# Control.net
KiCad netlist of a schematic drawn in Altium Designer
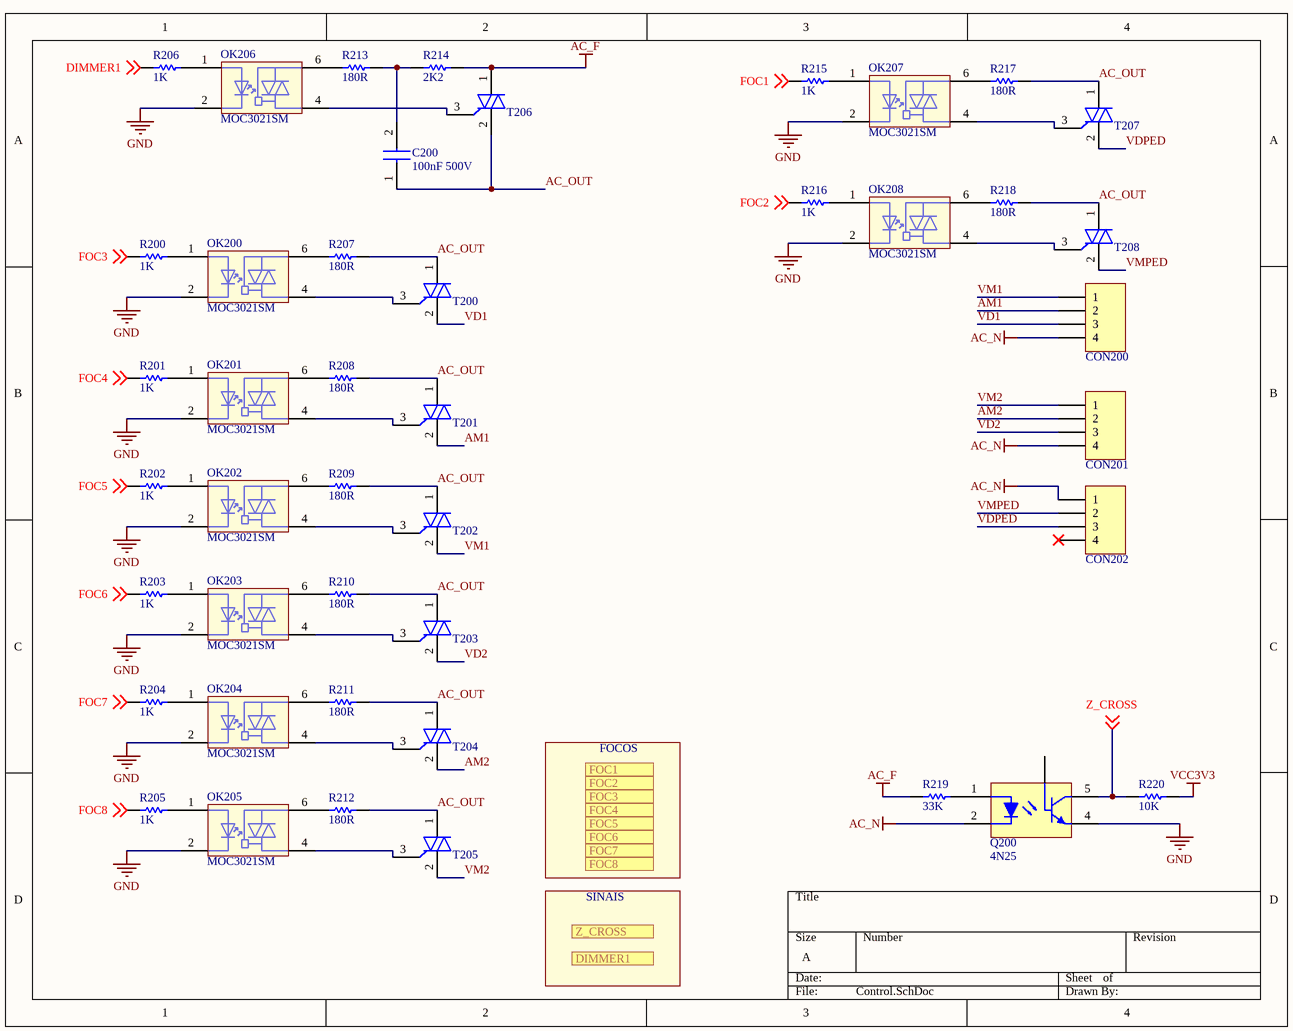
[diagram p0: Control.SchDoc]

(export (version "E")
  (design (tool "Eeschema 10.0.6"))
  (components
    (comp (ref "C200")
      (value "100nF 500V")
      (footprint "STL:CAPC3225-1210N")
      (description "CAP CER 0.1UF 500V X7R 1210")
      (fields
        (field (name "MANUFACTURER_PART_NUMBER") "C1210C106M6PACTU")
        (field (name "MOUSER PART NUMBER") "80-C1210C106M6P")
      )
      (libsource (lib "STL") (part "CAP 100nF 500V C1210C106M6PACTU 1210"))
    )
    (comp (ref "CON200")
      (value "TERM BLOCK 4POS")
      (footprint "STL:MSTBA 4G")
      (description "TERM BLOCK HDR 4POS R/A 5.08MM")
      (libsource (lib "STL") (part "TERM BLOCK HEADER 4POS R/A 5.08MM"))
    )
    (comp (ref "CON201")
      (value "TERM BLOCK 4POS")
      (footprint "STL:MSTBA 4G")
      (description "TERM BLOCK HDR 4POS R/A 5.08MM")
      (libsource (lib "STL") (part "TERM BLOCK HEADER 4POS R/A 5.08MM"))
    )
    (comp (ref "CON202")
      (value "TERM BLOCK 4POS")
      (footprint "STL:MSTBA 4G")
      (description "TERM BLOCK HDR 4POS R/A 5.08MM")
      (libsource (lib "STL") (part "TERM BLOCK HEADER 4POS R/A 5.08MM"))
    )
    (comp (ref "OK200")
      (value "MOC3021SM")
      (footprint "STL:SOP254P1016X450-6N")
      (description "OPTOCOUPLERS SMD-6 ROHS")
      (fields
        (field (name "MANUFACTURER PART NUMBER") "OR-MOC3021S")
        (field (name "MANUFACTURER") "Orient Technology")
      )
      (libsource (lib "STL") (part "OPTOISO Triac MOC3021SM SOP6N"))
    )
    (comp (ref "OK201")
      (value "MOC3021SM")
      (footprint "STL:SOP254P1016X450-6N")
      (description "OPTOCOUPLERS SMD-6 ROHS")
      (fields
        (field (name "MANUFACTURER PART NUMBER") "OR-MOC3021S")
        (field (name "MANUFACTURER") "Orient Technology")
      )
      (libsource (lib "STL") (part "OPTOISO Triac MOC3021SM SOP6N"))
    )
    (comp (ref "OK202")
      (value "MOC3021SM")
      (footprint "STL:SOP254P1016X450-6N")
      (description "OPTOCOUPLERS SMD-6 ROHS")
      (fields
        (field (name "MANUFACTURER PART NUMBER") "OR-MOC3021S")
        (field (name "MANUFACTURER") "Orient Technology")
      )
      (libsource (lib "STL") (part "OPTOISO Triac MOC3021SM SOP6N"))
    )
    (comp (ref "OK203")
      (value "MOC3021SM")
      (footprint "STL:SOP254P1016X450-6N")
      (description "OPTOCOUPLERS SMD-6 ROHS")
      (fields
        (field (name "MANUFACTURER PART NUMBER") "OR-MOC3021S")
        (field (name "MANUFACTURER") "Orient Technology")
      )
      (libsource (lib "STL") (part "OPTOISO Triac MOC3021SM SOP6N"))
    )
    (comp (ref "OK204")
      (value "MOC3021SM")
      (footprint "STL:SOP254P1016X450-6N")
      (description "OPTOCOUPLERS SMD-6 ROHS")
      (fields
        (field (name "MANUFACTURER PART NUMBER") "OR-MOC3021S")
        (field (name "MANUFACTURER") "Orient Technology")
      )
      (libsource (lib "STL") (part "OPTOISO Triac MOC3021SM SOP6N"))
    )
    (comp (ref "OK205")
      (value "MOC3021SM")
      (footprint "STL:SOP254P1016X450-6N")
      (description "OPTOCOUPLERS SMD-6 ROHS")
      (fields
        (field (name "MANUFACTURER PART NUMBER") "OR-MOC3021S")
        (field (name "MANUFACTURER") "Orient Technology")
      )
      (libsource (lib "STL") (part "OPTOISO Triac MOC3021SM SOP6N"))
    )
    (comp (ref "OK206")
      (value "MOC3021SM")
      (footprint "STL:SOP254P1016X450-6N")
      (description "OPTOCOUPLERS SMD-6 ROHS")
      (fields
        (field (name "MANUFACTURER PART NUMBER") "OR-MOC3021S")
        (field (name "MANUFACTURER") "Orient Technology")
      )
      (libsource (lib "STL") (part "OPTOISO Triac MOC3021SM SOP6N"))
    )
    (comp (ref "OK207")
      (value "MOC3021SM")
      (footprint "STL:SOP254P1016X450-6N")
      (description "OPTOCOUPLERS SMD-6 ROHS")
      (fields
        (field (name "MANUFACTURER PART NUMBER") "OR-MOC3021S")
        (field (name "MANUFACTURER") "Orient Technology")
      )
      (libsource (lib "STL") (part "OPTOISO Triac MOC3021SM SOP6N"))
    )
    (comp (ref "OK208")
      (value "MOC3021SM")
      (footprint "STL:SOP254P1016X450-6N")
      (description "OPTOCOUPLERS SMD-6 ROHS")
      (fields
        (field (name "MANUFACTURER PART NUMBER") "OR-MOC3021S")
        (field (name "MANUFACTURER") "Orient Technology")
      )
      (libsource (lib "STL") (part "OPTOISO Triac MOC3021SM SOP6N"))
    )
    (comp (ref "Q200")
      (value "4N25")
      (footprint "STL:6-SMD")
      (description "OPTOISO 4.17KV TRANS W/BASE 6SMD")
      (fields
        (field (name "MANUFACTURER") "ON Semiconductor")
        (field (name "MANUFACTURER PART NUMBER") "4N25SR2M")
      )
      (libsource (lib "STL") (part "OPTOISO 4N25S 2.5KV TRANS W/BASE 6SMD"))
    )
    (comp (ref "R200")
      (value "1K")
      (footprint "STL:CR2012-0805")
      (description "RES SMD 1K OHM 1% 1/8W 0805")
      (fields
        (field (name "MANUFACTURER") "Yageo")
        (field (name "MANUFACTURER PART NUMBER") "RC0805FR-071KL")
      )
      (libsource (lib "STL") (part "RES 1K OHM 1% 1/8W 0805 SMD"))
    )
    (comp (ref "R201")
      (value "1K")
      (footprint "STL:CR2012-0805")
      (description "RES SMD 1K OHM 1% 1/8W 0805")
      (fields
        (field (name "MANUFACTURER") "Yageo")
        (field (name "MANUFACTURER PART NUMBER") "RC0805FR-071KL")
      )
      (libsource (lib "STL") (part "RES 1K OHM 1% 1/8W 0805 SMD"))
    )
    (comp (ref "R202")
      (value "1K")
      (footprint "STL:CR2012-0805")
      (description "RES SMD 1K OHM 1% 1/8W 0805")
      (fields
        (field (name "MANUFACTURER") "Yageo")
        (field (name "MANUFACTURER PART NUMBER") "RC0805FR-071KL")
      )
      (libsource (lib "STL") (part "RES 1K OHM 1% 1/8W 0805 SMD"))
    )
    (comp (ref "R203")
      (value "1K")
      (footprint "STL:CR2012-0805")
      (description "RES SMD 1K OHM 1% 1/8W 0805")
      (fields
        (field (name "MANUFACTURER") "Yageo")
        (field (name "MANUFACTURER PART NUMBER") "RC0805FR-071KL")
      )
      (libsource (lib "STL") (part "RES 1K OHM 1% 1/8W 0805 SMD"))
    )
    (comp (ref "R204")
      (value "1K")
      (footprint "STL:CR2012-0805")
      (description "RES SMD 1K OHM 1% 1/8W 0805")
      (fields
        (field (name "MANUFACTURER") "Yageo")
        (field (name "MANUFACTURER PART NUMBER") "RC0805FR-071KL")
      )
      (libsource (lib "STL") (part "RES 1K OHM 1% 1/8W 0805 SMD"))
    )
    (comp (ref "R205")
      (value "1K")
      (footprint "STL:CR2012-0805")
      (description "RES SMD 1K OHM 1% 1/8W 0805")
      (fields
        (field (name "MANUFACTURER") "Yageo")
        (field (name "MANUFACTURER PART NUMBER") "RC0805FR-071KL")
      )
      (libsource (lib "STL") (part "RES 1K OHM 1% 1/8W 0805 SMD"))
    )
    (comp (ref "R206")
      (value "1K")
      (footprint "STL:CR2012-0805")
      (description "RES SMD 1K OHM 1% 1/8W 0805")
      (fields
        (field (name "MANUFACTURER") "Yageo")
        (field (name "MANUFACTURER PART NUMBER") "RC0805FR-071KL")
      )
      (libsource (lib "STL") (part "RES 1K OHM 1% 1/8W 0805 SMD"))
    )
    (comp (ref "R207")
      (value "180R")
      (footprint "STL:CR2012-0805")
      (description "RES 180 OHM 1/8W 5% 0805 SMD")
      (fields
        (field (name "MANUFACTURER") "Uniroyal")
        (field (name "MANUFACTURER PART NUMBER") "0805W8J0181T5E")
      )
      (libsource (lib "STL") (part "RES 180R 1/8W 5% 0805 SMD"))
    )
    (comp (ref "R208")
      (value "180R")
      (footprint "STL:CR2012-0805")
      (description "RES 180 OHM 1/8W 5% 0805 SMD")
      (fields
        (field (name "MANUFACTURER") "Uniroyal")
        (field (name "MANUFACTURER PART NUMBER") "0805W8J0181T5E")
      )
      (libsource (lib "STL") (part "RES 180R 1/8W 5% 0805 SMD"))
    )
    (comp (ref "R209")
      (value "180R")
      (footprint "STL:CR2012-0805")
      (description "RES 180 OHM 1/8W 5% 0805 SMD")
      (fields
        (field (name "MANUFACTURER") "Uniroyal")
        (field (name "MANUFACTURER PART NUMBER") "0805W8J0181T5E")
      )
      (libsource (lib "STL") (part "RES 180R 1/8W 5% 0805 SMD"))
    )
    (comp (ref "R210")
      (value "180R")
      (footprint "STL:CR2012-0805")
      (description "RES 180 OHM 1/8W 5% 0805 SMD")
      (fields
        (field (name "MANUFACTURER") "Uniroyal")
        (field (name "MANUFACTURER PART NUMBER") "0805W8J0181T5E")
      )
      (libsource (lib "STL") (part "RES 180R 1/8W 5% 0805 SMD"))
    )
    (comp (ref "R211")
      (value "180R")
      (footprint "STL:CR2012-0805")
      (description "RES 180 OHM 1/8W 5% 0805 SMD")
      (fields
        (field (name "MANUFACTURER") "Uniroyal")
        (field (name "MANUFACTURER PART NUMBER") "0805W8J0181T5E")
      )
      (libsource (lib "STL") (part "RES 180R 1/8W 5% 0805 SMD"))
    )
    (comp (ref "R212")
      (value "180R")
      (footprint "STL:CR2012-0805")
      (description "RES 180 OHM 1/8W 5% 0805 SMD")
      (fields
        (field (name "MANUFACTURER") "Uniroyal")
        (field (name "MANUFACTURER PART NUMBER") "0805W8J0181T5E")
      )
      (libsource (lib "STL") (part "RES 180R 1/8W 5% 0805 SMD"))
    )
    (comp (ref "R213")
      (value "180R")
      (footprint "STL:CR2012-0805")
      (description "RES 180 OHM 1/8W 5% 0805 SMD")
      (fields
        (field (name "MANUFACTURER") "Uniroyal")
        (field (name "MANUFACTURER PART NUMBER") "0805W8J0181T5E")
      )
      (libsource (lib "STL") (part "RES 180R 1/8W 5% 0805 SMD"))
    )
    (comp (ref "R214")
      (value "2K2")
      (footprint "STL:CR2012-0805")
      (description "RES SMD 2.2K OHM 5% 1/8W 0805")
      (fields
        (field (name "MANUFACTURER") "Panasonic Electronic Components")
        (field (name "PART#") "ERJ-6GEYJ222V")
      )
      (libsource (lib "STL") (part "RES 2K2 OHM 1/8W 5% 0805 SMD"))
    )
    (comp (ref "R215")
      (value "1K")
      (footprint "STL:CR2012-0805")
      (description "RES SMD 1K OHM 1% 1/8W 0805")
      (fields
        (field (name "MANUFACTURER") "Yageo")
        (field (name "MANUFACTURER PART NUMBER") "RC0805FR-071KL")
      )
      (libsource (lib "STL") (part "RES 1K OHM 1% 1/8W 0805 SMD"))
    )
    (comp (ref "R216")
      (value "1K")
      (footprint "STL:CR2012-0805")
      (description "RES SMD 1K OHM 1% 1/8W 0805")
      (fields
        (field (name "MANUFACTURER") "Yageo")
        (field (name "MANUFACTURER PART NUMBER") "RC0805FR-071KL")
      )
      (libsource (lib "STL") (part "RES 1K OHM 1% 1/8W 0805 SMD"))
    )
    (comp (ref "R217")
      (value "180R")
      (footprint "STL:CR2012-0805")
      (description "RES 180 OHM 1/8W 5% 0805 SMD")
      (fields
        (field (name "MANUFACTURER") "Uniroyal")
        (field (name "MANUFACTURER PART NUMBER") "0805W8J0181T5E")
      )
      (libsource (lib "STL") (part "RES 180R 1/8W 5% 0805 SMD"))
    )
    (comp (ref "R218")
      (value "180R")
      (footprint "STL:CR2012-0805")
      (description "RES 180 OHM 1/8W 5% 0805 SMD")
      (fields
        (field (name "MANUFACTURER") "Uniroyal")
        (field (name "MANUFACTURER PART NUMBER") "0805W8J0181T5E")
      )
      (libsource (lib "STL") (part "RES 180R 1/8W 5% 0805 SMD"))
    )
    (comp (ref "R219")
      (value "33K")
      (footprint "STL:CR2012-0805")
      (description "RES SMD 33K OHM 5% 1/8W 0805")
      (fields
        (field (name "MANUFACTURER") "Uniroyal")
        (field (name "MANUFACTURER PART NUMBER") "0805W8J0333T5E")
      )
      (libsource (lib "STL") (part "RES 33K OHM 5% 1/8W 0805 SMD"))
    )
    (comp (ref "R220")
      (value "10K")
      (footprint "STL:CR2012-0805")
      (description "RES 0805 10K Ohm 0.1% 1/10W  SMD")
      (fields
        (field (name "MANUFACTURER") "Panasonic Electronic Components")
        (field (name "MANUFACTURER PART NUMBER") "ERJ-6ENF1002V")
      )
      (libsource (lib "STL") (part "RES 10K OHM 1% 1/8W 0805 SMD"))
    )
    (comp (ref "T200")
      (value "BTA12-600BRG")
      (footprint "STL:TO255P460X1020X2005-3P")
      (description "Thyristor TRIAC 600V 126A 3-Pin(3+Tab) TO-220AB Insulated Tube")
      (fields
        (field (name "MOUSER PART NUMBER") "511-BTA12-600B")
        (field (name "MANUFACTURER") "STMicroelectronics")
      )
      (libsource (lib "STL") (part "THIRISTOR  TRIAC BTA12-600BRG TO220"))
    )
    (comp (ref "T201")
      (value "BTA12-600BRG")
      (footprint "STL:TO255P460X1020X2005-3P")
      (description "Thyristor TRIAC 600V 126A 3-Pin(3+Tab) TO-220AB Insulated Tube")
      (fields
        (field (name "MOUSER PART NUMBER") "511-BTA12-600B")
        (field (name "MANUFACTURER") "STMicroelectronics")
      )
      (libsource (lib "STL") (part "THIRISTOR  TRIAC BTA12-600BRG TO220"))
    )
    (comp (ref "T202")
      (value "BTA12-600BRG")
      (footprint "STL:TO255P460X1020X2005-3P")
      (description "Thyristor TRIAC 600V 126A 3-Pin(3+Tab) TO-220AB Insulated Tube")
      (fields
        (field (name "MOUSER PART NUMBER") "511-BTA12-600B")
        (field (name "MANUFACTURER") "STMicroelectronics")
      )
      (libsource (lib "STL") (part "THIRISTOR  TRIAC BTA12-600BRG TO220"))
    )
    (comp (ref "T203")
      (value "BTA12-600BRG")
      (footprint "STL:TO255P460X1020X2005-3P")
      (description "Thyristor TRIAC 600V 126A 3-Pin(3+Tab) TO-220AB Insulated Tube")
      (fields
        (field (name "MOUSER PART NUMBER") "511-BTA12-600B")
        (field (name "MANUFACTURER") "STMicroelectronics")
      )
      (libsource (lib "STL") (part "THIRISTOR  TRIAC BTA12-600BRG TO220"))
    )
    (comp (ref "T204")
      (value "BTA12-600BRG")
      (footprint "STL:TO255P460X1020X2005-3P")
      (description "Thyristor TRIAC 600V 126A 3-Pin(3+Tab) TO-220AB Insulated Tube")
      (fields
        (field (name "MOUSER PART NUMBER") "511-BTA12-600B")
        (field (name "MANUFACTURER") "STMicroelectronics")
      )
      (libsource (lib "STL") (part "THIRISTOR  TRIAC BTA12-600BRG TO220"))
    )
    (comp (ref "T205")
      (value "BTA12-600BRG")
      (footprint "STL:TO255P460X1020X2005-3P")
      (description "Thyristor TRIAC 600V 126A 3-Pin(3+Tab) TO-220AB Insulated Tube")
      (fields
        (field (name "MOUSER PART NUMBER") "511-BTA12-600B")
        (field (name "MANUFACTURER") "STMicroelectronics")
      )
      (libsource (lib "STL") (part "THIRISTOR  TRIAC BTA12-600BRG TO220"))
    )
    (comp (ref "T206")
      (value "BTA12-600BRG")
      (footprint "STL:TO255P460X1020X2005-3P")
      (description "Thyristor TRIAC 600V 126A 3-Pin(3+Tab) TO-220AB Insulated Tube")
      (fields
        (field (name "MOUSER PART NUMBER") "511-BTA12-600B")
        (field (name "MANUFACTURER") "STMicroelectronics")
      )
      (libsource (lib "STL") (part "THIRISTOR  TRIAC BTA12-600BRG TO220"))
    )
    (comp (ref "T207")
      (value "BTA12-600BRG")
      (footprint "STL:TO255P460X1020X2005-3P")
      (description "Thyristor TRIAC 600V 126A 3-Pin(3+Tab) TO-220AB Insulated Tube")
      (fields
        (field (name "MOUSER PART NUMBER") "511-BTA12-600B")
        (field (name "MANUFACTURER") "STMicroelectronics")
      )
      (libsource (lib "STL") (part "THIRISTOR  TRIAC BTA12-600BRG TO220"))
    )
    (comp (ref "T208")
      (value "BTA12-600BRG")
      (footprint "STL:TO255P460X1020X2005-3P")
      (description "Thyristor TRIAC 600V 126A 3-Pin(3+Tab) TO-220AB Insulated Tube")
      (fields
        (field (name "MOUSER PART NUMBER") "511-BTA12-600B")
        (field (name "MANUFACTURER") "STMicroelectronics")
      )
      (libsource (lib "STL") (part "THIRISTOR  TRIAC BTA12-600BRG TO220"))
    )
  )
  (nets
    (net (code "1") (name "/AC_OUT") (class "Default")
      (node (ref "C200") (pin "1") (pinfunction "1_1") (pintype "passive"))
      (node (ref "R207") (pin "2") (pinfunction "2_2") (pintype "passive"))
      (node (ref "R208") (pin "2") (pinfunction "2_2") (pintype "passive"))
      (node (ref "R209") (pin "2") (pinfunction "2_2") (pintype "passive"))
      (node (ref "R210") (pin "2") (pinfunction "2_2") (pintype "passive"))
      (node (ref "R211") (pin "2") (pinfunction "2_2") (pintype "passive"))
      (node (ref "R212") (pin "2") (pinfunction "2_2") (pintype "passive"))
      (node (ref "R217") (pin "2") (pinfunction "2_2") (pintype "passive"))
      (node (ref "R218") (pin "2") (pinfunction "2_2") (pintype "passive"))
      (node (ref "T200") (pin "1") (pinfunction "A1_1") (pintype "passive"))
      (node (ref "T201") (pin "1") (pinfunction "A1_1") (pintype "passive"))
      (node (ref "T202") (pin "1") (pinfunction "A1_1") (pintype "passive"))
      (node (ref "T203") (pin "1") (pinfunction "A1_1") (pintype "passive"))
      (node (ref "T204") (pin "1") (pinfunction "A1_1") (pintype "passive"))
      (node (ref "T205") (pin "1") (pinfunction "A1_1") (pintype "passive"))
      (node (ref "T206") (pin "2") (pinfunction "A2_2") (pintype "passive"))
      (node (ref "T207") (pin "1") (pinfunction "A1_1") (pintype "passive"))
      (node (ref "T208") (pin "1") (pinfunction "A1_1") (pintype "passive"))
    )
    (net (code "2") (name "/AM1") (class "Default")
      (node (ref "CON200") (pin "2") (pinfunction "2_2") (pintype "passive"))
      (node (ref "T201") (pin "2") (pinfunction "A2_2") (pintype "passive"))
    )
    (net (code "3") (name "/AM2") (class "Default")
      (node (ref "CON201") (pin "2") (pinfunction "2_2") (pintype "passive"))
      (node (ref "T204") (pin "2") (pinfunction "A2_2") (pintype "passive"))
    )
    (net (code "4") (name "/VD1") (class "Default")
      (node (ref "CON200") (pin "3") (pinfunction "3_3") (pintype "passive"))
      (node (ref "T200") (pin "2") (pinfunction "A2_2") (pintype "passive"))
    )
    (net (code "5") (name "/VD2") (class "Default")
      (node (ref "CON201") (pin "3") (pinfunction "3_3") (pintype "passive"))
      (node (ref "T203") (pin "2") (pinfunction "A2_2") (pintype "passive"))
    )
    (net (code "6") (name "/VDPED") (class "Default")
      (node (ref "CON202") (pin "3") (pinfunction "3_3") (pintype "passive"))
      (node (ref "T207") (pin "2") (pinfunction "A2_2") (pintype "passive"))
    )
    (net (code "7") (name "/VM1") (class "Default")
      (node (ref "CON200") (pin "1") (pinfunction "1_1") (pintype "passive"))
      (node (ref "T202") (pin "2") (pinfunction "A2_2") (pintype "passive"))
    )
    (net (code "8") (name "/VM2") (class "Default")
      (node (ref "CON201") (pin "1") (pinfunction "1_1") (pintype "passive"))
      (node (ref "T205") (pin "2") (pinfunction "A2_2") (pintype "passive"))
    )
    (net (code "9") (name "/VMPED") (class "Default")
      (node (ref "CON202") (pin "2") (pinfunction "2_2") (pintype "passive"))
      (node (ref "T208") (pin "2") (pinfunction "A2_2") (pintype "passive"))
    )
    (net (code "10") (name "AC_F") (class "Default")
      (node (ref "R214") (pin "2") (pinfunction "2_2") (pintype "passive"))
      (node (ref "R219") (pin "1") (pinfunction "1_1") (pintype "passive"))
      (node (ref "T206") (pin "1") (pinfunction "A1_1") (pintype "passive"))
    )
    (net (code "11") (name "AC_N") (class "Default")
      (node (ref "CON200") (pin "4") (pinfunction "4_4") (pintype "passive"))
      (node (ref "CON201") (pin "4") (pinfunction "4_4") (pintype "passive"))
      (node (ref "CON202") (pin "1") (pinfunction "1_1") (pintype "passive"))
      (node (ref "Q200") (pin "2") (pinfunction "K_2") (pintype "passive"))
    )
    (net (code "12") (name "DIMMER1") (class "Default")
      (node (ref "R206") (pin "1") (pinfunction "1_1") (pintype "passive"))
    )
    (net (code "13") (name "FOC1") (class "Default")
      (node (ref "R215") (pin "1") (pinfunction "1_1") (pintype "passive"))
    )
    (net (code "14") (name "FOC2") (class "Default")
      (node (ref "R216") (pin "1") (pinfunction "1_1") (pintype "passive"))
    )
    (net (code "15") (name "FOC3") (class "Default")
      (node (ref "R200") (pin "1") (pinfunction "1_1") (pintype "passive"))
    )
    (net (code "16") (name "FOC4") (class "Default")
      (node (ref "R201") (pin "1") (pinfunction "1_1") (pintype "passive"))
    )
    (net (code "17") (name "FOC5") (class "Default")
      (node (ref "R202") (pin "1") (pinfunction "1_1") (pintype "passive"))
    )
    (net (code "18") (name "FOC6") (class "Default")
      (node (ref "R203") (pin "1") (pinfunction "1_1") (pintype "passive"))
    )
    (net (code "19") (name "FOC7") (class "Default")
      (node (ref "R204") (pin "1") (pinfunction "1_1") (pintype "passive"))
    )
    (net (code "20") (name "FOC8") (class "Default")
      (node (ref "R205") (pin "1") (pinfunction "1_1") (pintype "passive"))
    )
    (net (code "21") (name "GND") (class "Default")
      (node (ref "OK200") (pin "2") (pinfunction "K_2") (pintype "passive"))
      (node (ref "OK201") (pin "2") (pinfunction "K_2") (pintype "passive"))
      (node (ref "OK202") (pin "2") (pinfunction "K_2") (pintype "passive"))
      (node (ref "OK203") (pin "2") (pinfunction "K_2") (pintype "passive"))
      (node (ref "OK204") (pin "2") (pinfunction "K_2") (pintype "passive"))
      (node (ref "OK205") (pin "2") (pinfunction "K_2") (pintype "passive"))
      (node (ref "OK206") (pin "2") (pinfunction "K_2") (pintype "passive"))
      (node (ref "OK207") (pin "2") (pinfunction "K_2") (pintype "passive"))
      (node (ref "OK208") (pin "2") (pinfunction "K_2") (pintype "passive"))
      (node (ref "Q200") (pin "4") (pinfunction "E_4") (pintype "passive"))
    )
    (net (code "22") (name "Net-(C200-Pad2)") (class "Default")
      (node (ref "C200") (pin "2") (pinfunction "2_2") (pintype "passive"))
      (node (ref "R213") (pin "2") (pinfunction "2_2") (pintype "passive"))
      (node (ref "R214") (pin "1") (pinfunction "1_1") (pintype "passive"))
    )
    (net (code "23") (name "Net-(OK200-A)") (class "Default")
      (node (ref "OK200") (pin "1") (pinfunction "A_1") (pintype "passive"))
      (node (ref "R200") (pin "2") (pinfunction "2_2") (pintype "passive"))
    )
    (net (code "24") (name "Net-(OK200-A{slash}K)") (class "Default")
      (node (ref "OK200") (pin "4") (pinfunction "A/K_4") (pintype "passive"))
      (node (ref "T200") (pin "3") (pinfunction "G_3") (pintype "passive"))
    )
    (net (code "25") (name "Net-(OK200-K{slash}A)") (class "Default")
      (node (ref "OK200") (pin "6") (pinfunction "K/A_6") (pintype "passive"))
      (node (ref "R207") (pin "1") (pinfunction "1_1") (pintype "passive"))
    )
    (net (code "26") (name "Net-(OK201-A)") (class "Default")
      (node (ref "OK201") (pin "1") (pinfunction "A_1") (pintype "passive"))
      (node (ref "R201") (pin "2") (pinfunction "2_2") (pintype "passive"))
    )
    (net (code "27") (name "Net-(OK201-A{slash}K)") (class "Default")
      (node (ref "OK201") (pin "4") (pinfunction "A/K_4") (pintype "passive"))
      (node (ref "T201") (pin "3") (pinfunction "G_3") (pintype "passive"))
    )
    (net (code "28") (name "Net-(OK201-K{slash}A)") (class "Default")
      (node (ref "OK201") (pin "6") (pinfunction "K/A_6") (pintype "passive"))
      (node (ref "R208") (pin "1") (pinfunction "1_1") (pintype "passive"))
    )
    (net (code "29") (name "Net-(OK202-A)") (class "Default")
      (node (ref "OK202") (pin "1") (pinfunction "A_1") (pintype "passive"))
      (node (ref "R202") (pin "2") (pinfunction "2_2") (pintype "passive"))
    )
    (net (code "30") (name "Net-(OK202-A{slash}K)") (class "Default")
      (node (ref "OK202") (pin "4") (pinfunction "A/K_4") (pintype "passive"))
      (node (ref "T202") (pin "3") (pinfunction "G_3") (pintype "passive"))
    )
    (net (code "31") (name "Net-(OK202-K{slash}A)") (class "Default")
      (node (ref "OK202") (pin "6") (pinfunction "K/A_6") (pintype "passive"))
      (node (ref "R209") (pin "1") (pinfunction "1_1") (pintype "passive"))
    )
    (net (code "32") (name "Net-(OK203-A)") (class "Default")
      (node (ref "OK203") (pin "1") (pinfunction "A_1") (pintype "passive"))
      (node (ref "R203") (pin "2") (pinfunction "2_2") (pintype "passive"))
    )
    (net (code "33") (name "Net-(OK203-A{slash}K)") (class "Default")
      (node (ref "OK203") (pin "4") (pinfunction "A/K_4") (pintype "passive"))
      (node (ref "T203") (pin "3") (pinfunction "G_3") (pintype "passive"))
    )
    (net (code "34") (name "Net-(OK203-K{slash}A)") (class "Default")
      (node (ref "OK203") (pin "6") (pinfunction "K/A_6") (pintype "passive"))
      (node (ref "R210") (pin "1") (pinfunction "1_1") (pintype "passive"))
    )
    (net (code "35") (name "Net-(OK204-A)") (class "Default")
      (node (ref "OK204") (pin "1") (pinfunction "A_1") (pintype "passive"))
      (node (ref "R204") (pin "2") (pinfunction "2_2") (pintype "passive"))
    )
    (net (code "36") (name "Net-(OK204-A{slash}K)") (class "Default")
      (node (ref "OK204") (pin "4") (pinfunction "A/K_4") (pintype "passive"))
      (node (ref "T204") (pin "3") (pinfunction "G_3") (pintype "passive"))
    )
    (net (code "37") (name "Net-(OK204-K{slash}A)") (class "Default")
      (node (ref "OK204") (pin "6") (pinfunction "K/A_6") (pintype "passive"))
      (node (ref "R211") (pin "1") (pinfunction "1_1") (pintype "passive"))
    )
    (net (code "38") (name "Net-(OK205-A)") (class "Default")
      (node (ref "OK205") (pin "1") (pinfunction "A_1") (pintype "passive"))
      (node (ref "R205") (pin "2") (pinfunction "2_2") (pintype "passive"))
    )
    (net (code "39") (name "Net-(OK205-A{slash}K)") (class "Default")
      (node (ref "OK205") (pin "4") (pinfunction "A/K_4") (pintype "passive"))
      (node (ref "T205") (pin "3") (pinfunction "G_3") (pintype "passive"))
    )
    (net (code "40") (name "Net-(OK205-K{slash}A)") (class "Default")
      (node (ref "OK205") (pin "6") (pinfunction "K/A_6") (pintype "passive"))
      (node (ref "R212") (pin "1") (pinfunction "1_1") (pintype "passive"))
    )
    (net (code "41") (name "Net-(OK206-A)") (class "Default")
      (node (ref "OK206") (pin "1") (pinfunction "A_1") (pintype "passive"))
      (node (ref "R206") (pin "2") (pinfunction "2_2") (pintype "passive"))
    )
    (net (code "42") (name "Net-(OK206-A{slash}K)") (class "Default")
      (node (ref "OK206") (pin "4") (pinfunction "A/K_4") (pintype "passive"))
      (node (ref "T206") (pin "3") (pinfunction "G_3") (pintype "passive"))
    )
    (net (code "43") (name "Net-(OK206-K{slash}A)") (class "Default")
      (node (ref "OK206") (pin "6") (pinfunction "K/A_6") (pintype "passive"))
      (node (ref "R213") (pin "1") (pinfunction "1_1") (pintype "passive"))
    )
    (net (code "44") (name "Net-(OK207-A)") (class "Default")
      (node (ref "OK207") (pin "1") (pinfunction "A_1") (pintype "passive"))
      (node (ref "R215") (pin "2") (pinfunction "2_2") (pintype "passive"))
    )
    (net (code "45") (name "Net-(OK207-A{slash}K)") (class "Default")
      (node (ref "OK207") (pin "4") (pinfunction "A/K_4") (pintype "passive"))
      (node (ref "T207") (pin "3") (pinfunction "G_3") (pintype "passive"))
    )
    (net (code "46") (name "Net-(OK207-K{slash}A)") (class "Default")
      (node (ref "OK207") (pin "6") (pinfunction "K/A_6") (pintype "passive"))
      (node (ref "R217") (pin "1") (pinfunction "1_1") (pintype "passive"))
    )
    (net (code "47") (name "Net-(OK208-A)") (class "Default")
      (node (ref "OK208") (pin "1") (pinfunction "A_1") (pintype "passive"))
      (node (ref "R216") (pin "2") (pinfunction "2_2") (pintype "passive"))
    )
    (net (code "48") (name "Net-(OK208-A{slash}K)") (class "Default")
      (node (ref "OK208") (pin "4") (pinfunction "A/K_4") (pintype "passive"))
      (node (ref "T208") (pin "3") (pinfunction "G_3") (pintype "passive"))
    )
    (net (code "49") (name "Net-(OK208-K{slash}A)") (class "Default")
      (node (ref "OK208") (pin "6") (pinfunction "K/A_6") (pintype "passive"))
      (node (ref "R218") (pin "1") (pinfunction "1_1") (pintype "passive"))
    )
    (net (code "50") (name "Net-(Q200-A)") (class "Default")
      (node (ref "Q200") (pin "1") (pinfunction "A_1") (pintype "passive"))
      (node (ref "R219") (pin "2") (pinfunction "2_2") (pintype "passive"))
    )
    (net (code "51") (name "VCC3V3") (class "Default")
      (node (ref "R220") (pin "2") (pinfunction "2_2") (pintype "passive"))
    )
    (net (code "52") (name "Z_CROSS") (class "Default")
      (node (ref "Q200") (pin "5") (pinfunction "C_5") (pintype "passive"))
      (node (ref "R220") (pin "1") (pinfunction "1_1") (pintype "passive"))
    )
    (net (code "53") (name "unconnected-(CON202-Pad4)") (class "Default")
      (node (ref "CON202") (pin "4") (pinfunction "4_4") (pintype "passive+no_connect"))
    )
    (net (code "54") (name "unconnected-(Q200-B-Pad6)") (class "Default")
      (node (ref "Q200") (pin "6") (pinfunction "B_6") (pintype "passive"))
    )
  )
)
